# steering_wheel_V3_0.net
KiCad netlist of a schematic drawn in EAGLE
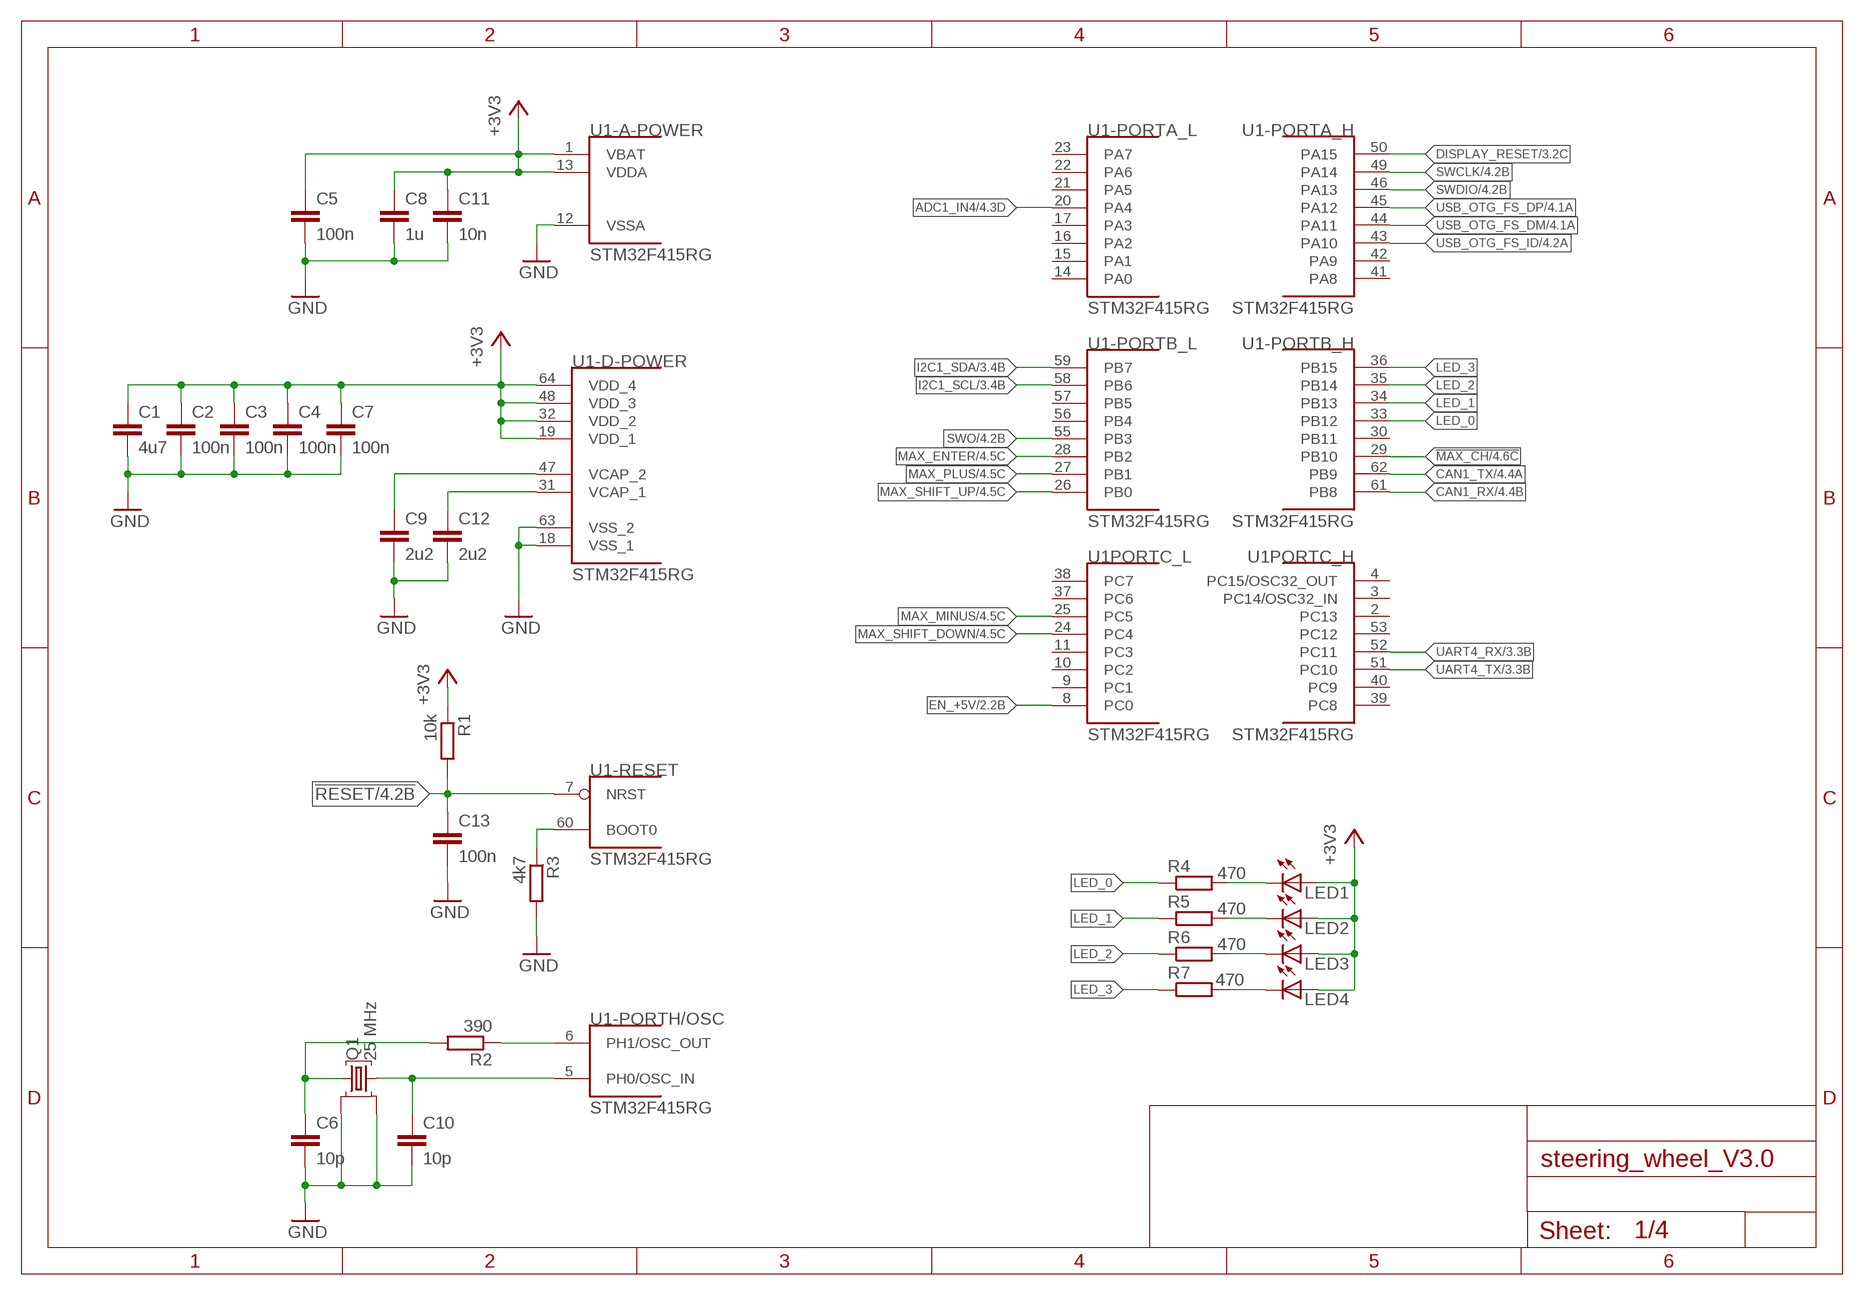
[diagram p0: schematic, sheet 1]
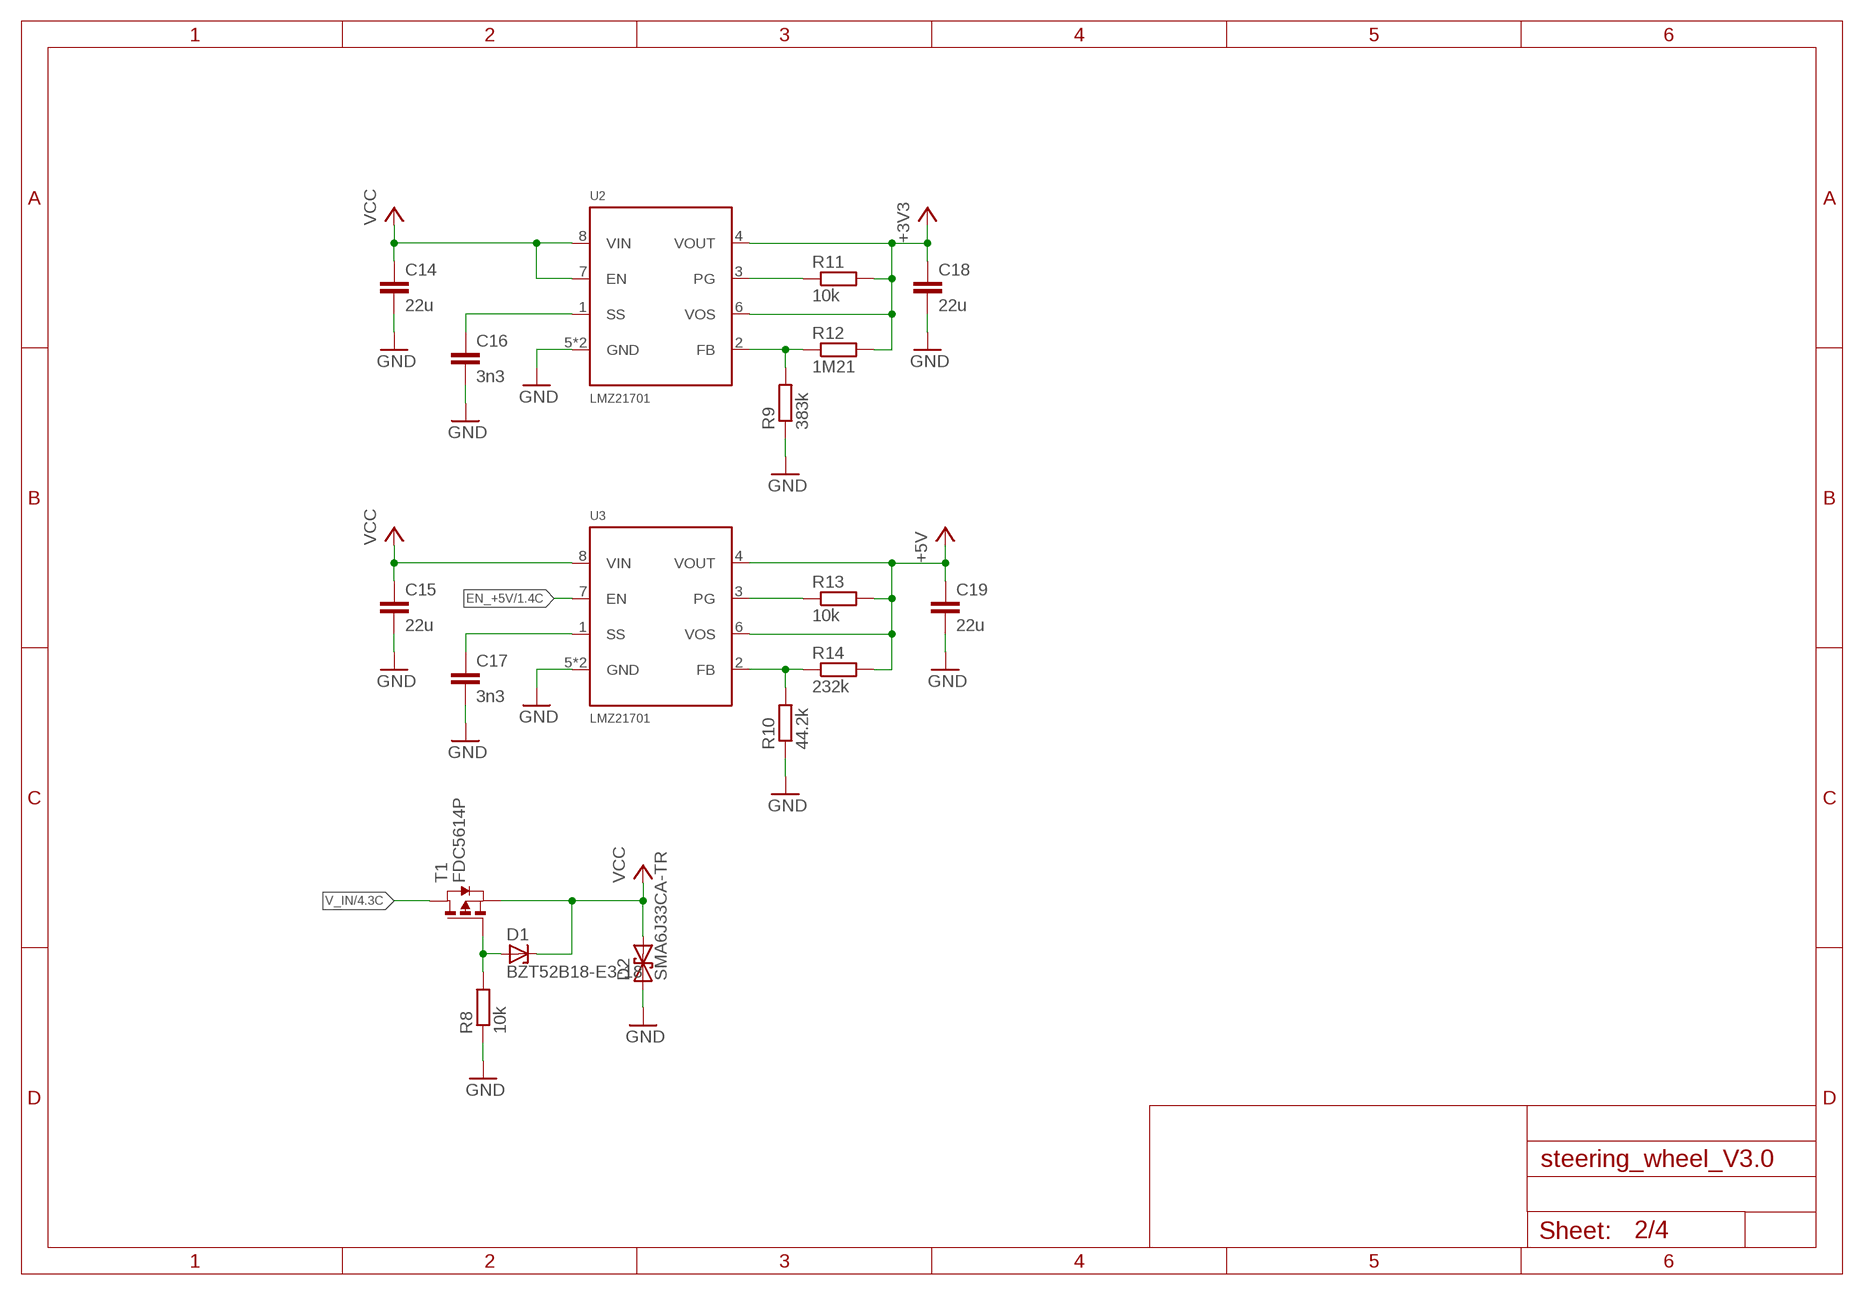
[diagram p1: schematic, sheet 2]
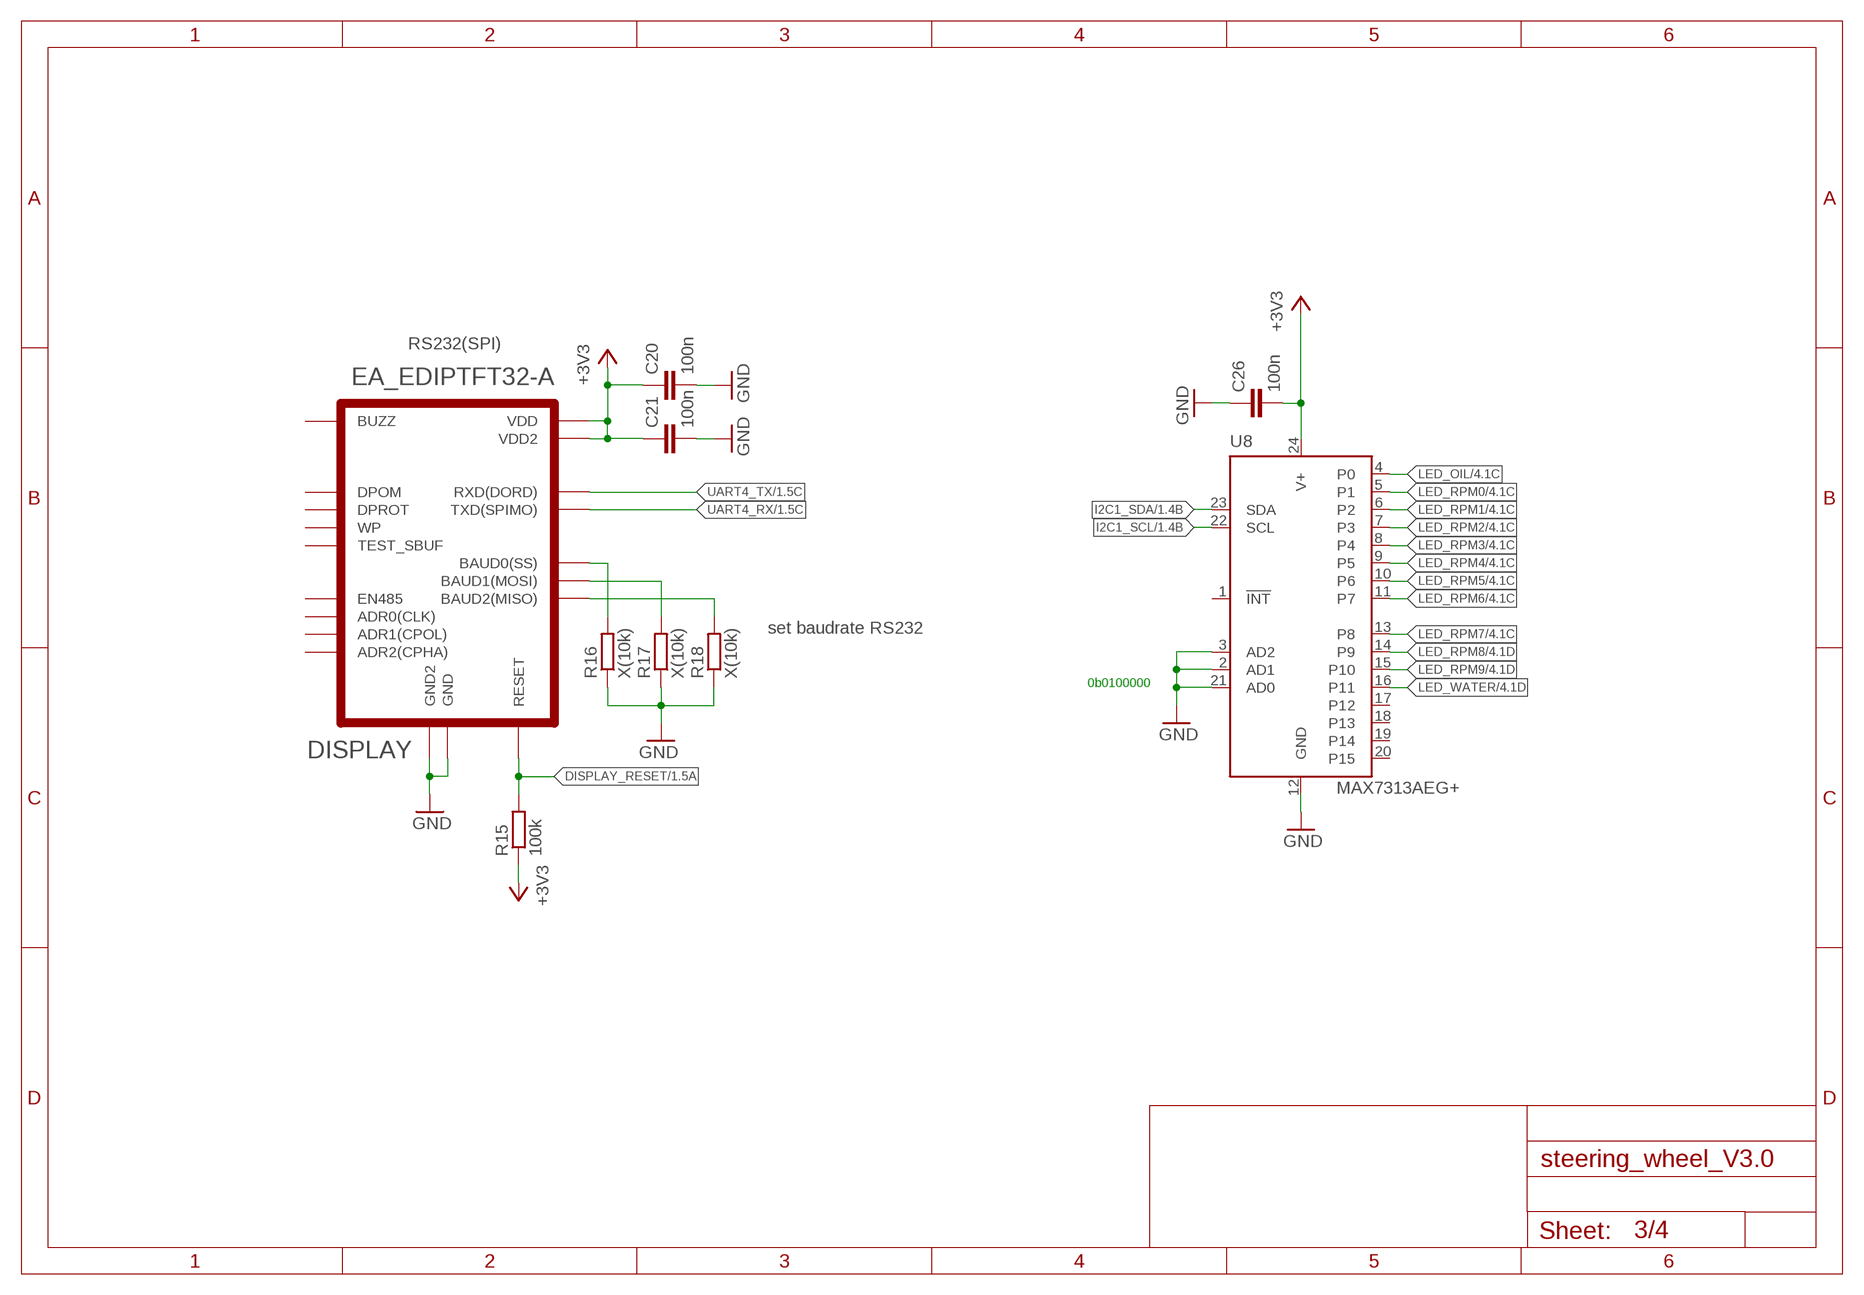
[diagram p2: schematic, sheet 3]
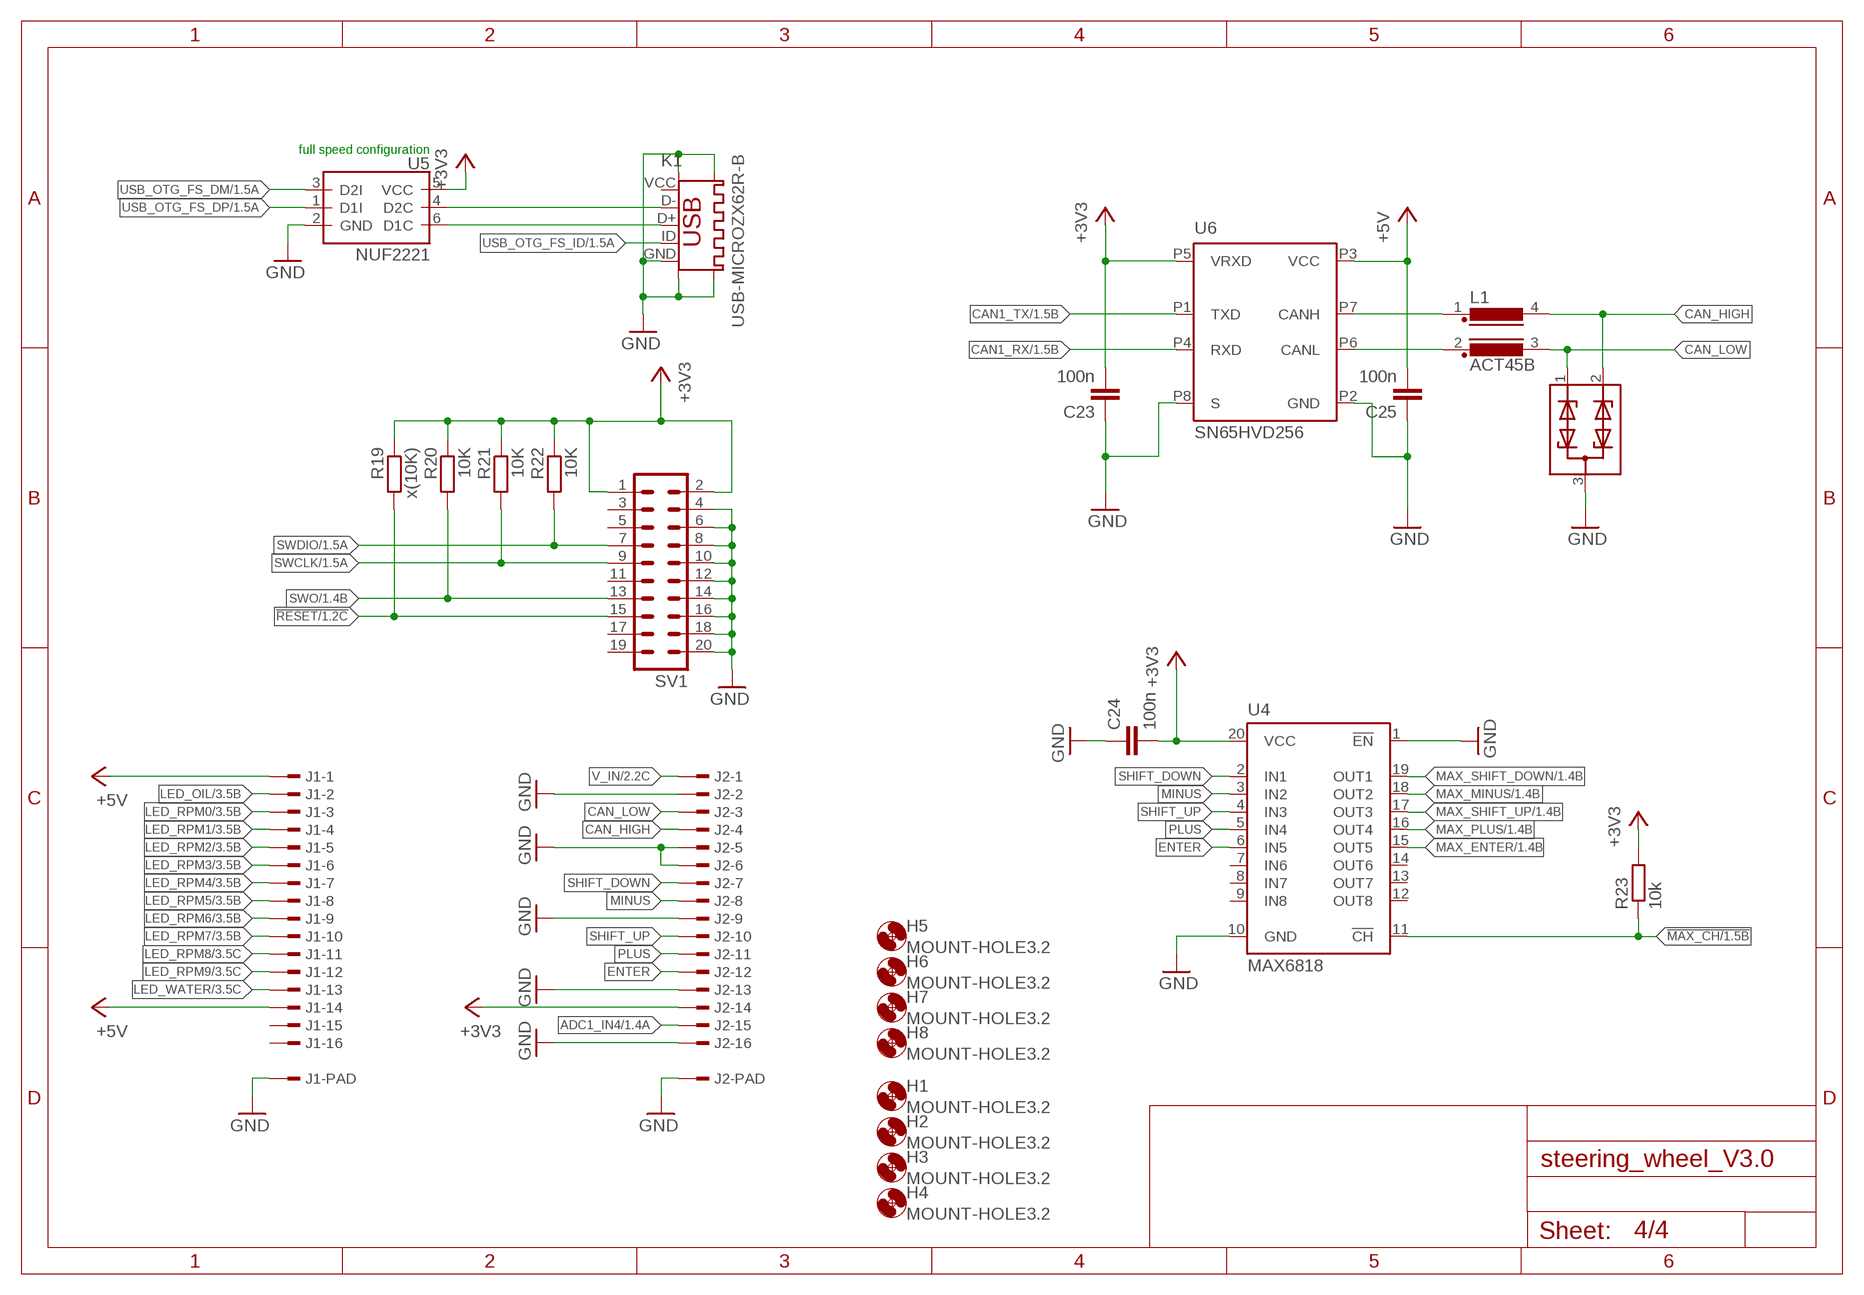
[diagram p3: schematic, sheet 4]

(export (version "E")
  (design (tool "Eeschema 10.0.6"))
  (components
    (comp (ref "C14")
      (value "22u")
      (footprint "eagle-import:C1210")
      (libsource (lib "eagle-import") (part "C-EUC1210"))
    )
    (comp (ref "C15")
      (value "22u")
      (footprint "eagle-import:C1210")
      (libsource (lib "eagle-import") (part "C-EUC1210"))
    )
    (comp (ref "C16")
      (value "3n3")
      (footprint "eagle-import:C0603")
      (libsource (lib "eagle-import") (part "C-EUC0603"))
    )
    (comp (ref "C17")
      (value "3n3")
      (footprint "eagle-import:C0603")
      (libsource (lib "eagle-import") (part "C-EUC0603"))
    )
    (comp (ref "C18")
      (value "22u")
      (footprint "eagle-import:C1210")
      (libsource (lib "eagle-import") (part "C-EUC1210"))
    )
    (comp (ref "C19")
      (value "22u")
      (footprint "eagle-import:C1210")
      (libsource (lib "eagle-import") (part "C-EUC1210"))
    )
    (comp (ref "D1")
      (value "BZT52B18-E3-18")
      (footprint "eagle-import:SOD123F")
      (libsource (lib "eagle-import") (part "ZENER_SOD123"))
    )
    (comp (ref "D2")
      (value "SMA6J33CA-TR")
      (footprint "eagle-import:DO214AC")
      (libsource (lib "eagle-import") (part "SMA6J33CA-TR"))
    )
    (comp (ref "R8")
      (value "10k")
      (footprint "eagle-import:R0603")
      (libsource (lib "eagle-import") (part "R-EU_R0603"))
    )
    (comp (ref "R9")
      (value "383k")
      (footprint "eagle-import:R0603")
      (libsource (lib "eagle-import") (part "R-EU_R0603"))
    )
    (comp (ref "R10")
      (value "44.2k")
      (footprint "eagle-import:R0603")
      (libsource (lib "eagle-import") (part "R-EU_R0603"))
    )
    (comp (ref "R11")
      (value "10k")
      (footprint "eagle-import:R0603")
      (libsource (lib "eagle-import") (part "R-EU_R0603"))
    )
    (comp (ref "R12")
      (value "1M21")
      (footprint "eagle-import:R0603")
      (libsource (lib "eagle-import") (part "R-EU_R0603"))
    )
    (comp (ref "R13")
      (value "10k")
      (footprint "eagle-import:R0603")
      (libsource (lib "eagle-import") (part "R-EU_R0603"))
    )
    (comp (ref "R14")
      (value "232k")
      (footprint "eagle-import:R0603")
      (libsource (lib "eagle-import") (part "R-EU_R0603"))
    )
    (comp (ref "T1")
      (value "FDC5614P")
      (footprint "eagle-import:SSOT6")
      (libsource (lib "eagle-import") (part "FDC5614P"))
    )
    (comp (ref "U2")
      (value "LMZ21701")
      (footprint "eagle-import:SIL0008E")
      (libsource (lib "eagle-import") (part "LMZ21701"))
    )
    (comp (ref "U3")
      (value "LMZ21701")
      (footprint "eagle-import:SIL0008E")
      (libsource (lib "eagle-import") (part "LMZ21701"))
    )
    (comp (ref "C23")
      (value "100n")
      (footprint "eagle-import:C0603")
      (libsource (lib "eagle-import") (part "C-EUC0603"))
    )
    (comp (ref "C24")
      (value "100n")
      (footprint "eagle-import:C0603")
      (libsource (lib "eagle-import") (part "C-EUC0603"))
    )
    (comp (ref "C25")
      (value "100n")
      (footprint "eagle-import:C0603")
      (libsource (lib "eagle-import") (part "C-EUC0603"))
    )
    (comp (ref "D3")
      (value "PESD1CAN-U")
      (footprint "eagle-import:SOT-323")
      (libsource (lib "eagle-import") (part "PESD1CAN-U"))
    )
    (comp (ref "H1")
      (value "MOUNT-HOLE3.2")
      (footprint "eagle-import:3,2")
      (libsource (lib "eagle-import") (part "MOUNT-HOLE3.2"))
    )
    (comp (ref "H2")
      (value "MOUNT-HOLE3.2")
      (footprint "eagle-import:3,2")
      (libsource (lib "eagle-import") (part "MOUNT-HOLE3.2"))
    )
    (comp (ref "H3")
      (value "MOUNT-HOLE3.2")
      (footprint "eagle-import:3,2")
      (libsource (lib "eagle-import") (part "MOUNT-HOLE3.2"))
    )
    (comp (ref "H4")
      (value "MOUNT-HOLE3.2")
      (footprint "eagle-import:3,2")
      (libsource (lib "eagle-import") (part "MOUNT-HOLE3.2"))
    )
    (comp (ref "H5")
      (value "MOUNT-HOLE3.2")
      (footprint "eagle-import:3,2")
      (libsource (lib "eagle-import") (part "MOUNT-HOLE3.2"))
    )
    (comp (ref "H6")
      (value "MOUNT-HOLE3.2")
      (footprint "eagle-import:3,2")
      (libsource (lib "eagle-import") (part "MOUNT-HOLE3.2"))
    )
    (comp (ref "H7")
      (value "MOUNT-HOLE3.2")
      (footprint "eagle-import:3,2")
      (libsource (lib "eagle-import") (part "MOUNT-HOLE3.2"))
    )
    (comp (ref "H8")
      (value "MOUNT-HOLE3.2")
      (footprint "eagle-import:3,2")
      (libsource (lib "eagle-import") (part "MOUNT-HOLE3.2"))
    )
    (comp (ref "J1")
      (value "1-292227-6")
      (footprint "eagle-import:1-292227-6")
      (libsource (lib "eagle-import") (part "1-292227-6"))
    )
    (comp (ref "J2")
      (value "1-292227-6")
      (footprint "eagle-import:1-292227-6")
      (libsource (lib "eagle-import") (part "1-292227-6"))
    )
    (comp (ref "K1")
      (value "USB-MICROZX62R-B")
      (footprint "eagle-import:ZX62R-B")
      (libsource (lib "eagle-import") (part "USB-MICROZX62R-B"))
    )
    (comp (ref "L1")
      (value "ACT45B")
      (footprint "eagle-import:ACT45B")
      (libsource (lib "eagle-import") (part "ACT45B"))
    )
    (comp (ref "R19")
      (value "x(10K)")
      (footprint "eagle-import:R0603")
      (libsource (lib "eagle-import") (part "R-EU_R0603"))
    )
    (comp (ref "R20")
      (value "10K")
      (footprint "eagle-import:R0603")
      (libsource (lib "eagle-import") (part "R-EU_R0603"))
    )
    (comp (ref "R21")
      (value "10K")
      (footprint "eagle-import:R0603")
      (libsource (lib "eagle-import") (part "R-EU_R0603"))
    )
    (comp (ref "R22")
      (value "10K")
      (footprint "eagle-import:R0603")
      (libsource (lib "eagle-import") (part "R-EU_R0603"))
    )
    (comp (ref "R23")
      (value "10k")
      (footprint "eagle-import:R0603")
      (libsource (lib "eagle-import") (part "R-EU_R0603"))
    )
    (comp (ref "SV1")
      (value "ML20")
      (footprint "eagle-import:ML20")
      (libsource (lib "eagle-import") (part "ML20"))
    )
    (comp (ref "U4")
      (value "MAX6818")
      (footprint "eagle-import:SSOP-20")
      (libsource (lib "eagle-import") (part "MAX6818"))
    )
    (comp (ref "U5")
      (value "NUF2221")
      (footprint "eagle-import:SOT363")
      (fields
        (field (name "OC_DIGIKEY") "NUF2221W1T2GOSCT-ND")
        (field (name "ORDER_CODE") "NUF2221W1T2GOSCT-ND")
      )
      (libsource (lib "eagle-import") (part "NUF2221"))
    )
    (comp (ref "U6")
      (value "SN65HVD256")
      (footprint "eagle-import:SOIC8")
      (libsource (lib "eagle-import") (part "SN65HVD256"))
    )
    (comp (ref "C1")
      (value "4u7")
      (footprint "eagle-import:C0603")
      (libsource (lib "eagle-import") (part "C-EUC0603"))
    )
    (comp (ref "C2")
      (value "100n")
      (footprint "eagle-import:C0603")
      (libsource (lib "eagle-import") (part "C-EUC0603"))
    )
    (comp (ref "C3")
      (value "100n")
      (footprint "eagle-import:C0603")
      (libsource (lib "eagle-import") (part "C-EUC0603"))
    )
    (comp (ref "C4")
      (value "100n")
      (footprint "eagle-import:C0603")
      (libsource (lib "eagle-import") (part "C-EUC0603"))
    )
    (comp (ref "C5")
      (value "100n")
      (footprint "eagle-import:C0603")
      (libsource (lib "eagle-import") (part "C-EUC0603"))
    )
    (comp (ref "C6")
      (value "10p")
      (footprint "eagle-import:C0603")
      (libsource (lib "eagle-import") (part "C-EUC0603"))
    )
    (comp (ref "C7")
      (value "100n")
      (footprint "eagle-import:C0603")
      (libsource (lib "eagle-import") (part "C-EUC0603"))
    )
    (comp (ref "C8")
      (value "1u")
      (footprint "eagle-import:C0603")
      (libsource (lib "eagle-import") (part "C-EUC0603"))
    )
    (comp (ref "C9")
      (value "2u2")
      (footprint "eagle-import:C0603")
      (libsource (lib "eagle-import") (part "C-EUC0603"))
    )
    (comp (ref "C10")
      (value "10p")
      (footprint "eagle-import:C0603")
      (libsource (lib "eagle-import") (part "C-EUC0603"))
    )
    (comp (ref "C11")
      (value "10n")
      (footprint "eagle-import:C0603")
      (libsource (lib "eagle-import") (part "C-EUC0603"))
    )
    (comp (ref "C12")
      (value "2u2")
      (footprint "eagle-import:C0603")
      (libsource (lib "eagle-import") (part "C-EUC0603"))
    )
    (comp (ref "C13")
      (value "100n")
      (footprint "eagle-import:C0603")
      (libsource (lib "eagle-import") (part "C-EUC0603"))
    )
    (comp (ref "LED1")
      (value "LEDCHIPLED_0603")
      (footprint "eagle-import:CHIPLED_0603")
      (libsource (lib "eagle-import") (part "LEDCHIPLED_0603"))
    )
    (comp (ref "LED2")
      (value "LEDCHIPLED_0603")
      (footprint "eagle-import:CHIPLED_0603")
      (libsource (lib "eagle-import") (part "LEDCHIPLED_0603"))
    )
    (comp (ref "LED3")
      (value "LEDCHIPLED_0603")
      (footprint "eagle-import:CHIPLED_0603")
      (libsource (lib "eagle-import") (part "LEDCHIPLED_0603"))
    )
    (comp (ref "LED4")
      (value "LEDCHIPLED_0603")
      (footprint "eagle-import:CHIPLED_0603")
      (libsource (lib "eagle-import") (part "LEDCHIPLED_0603"))
    )
    (comp (ref "Q1")
      (value "25 MHz")
      (footprint "eagle-import:3.2X2.5MM-SMD")
      (libsource (lib "eagle-import") (part "CRYSTAL2M_CX32"))
    )
    (comp (ref "R1")
      (value "10k")
      (footprint "eagle-import:R0603")
      (libsource (lib "eagle-import") (part "R-EU_R0603"))
    )
    (comp (ref "R2")
      (value "390")
      (footprint "eagle-import:R0603")
      (libsource (lib "eagle-import") (part "R-EU_R0603"))
    )
    (comp (ref "R3")
      (value "4k7")
      (footprint "eagle-import:R0603")
      (libsource (lib "eagle-import") (part "R-EU_R0603"))
    )
    (comp (ref "R4")
      (value "470")
      (footprint "eagle-import:R0603")
      (libsource (lib "eagle-import") (part "R-EU_R0603"))
    )
    (comp (ref "R5")
      (value "470")
      (footprint "eagle-import:R0603")
      (libsource (lib "eagle-import") (part "R-EU_R0603"))
    )
    (comp (ref "R6")
      (value "470")
      (footprint "eagle-import:R0603")
      (libsource (lib "eagle-import") (part "R-EU_R0603"))
    )
    (comp (ref "R7")
      (value "470")
      (footprint "eagle-import:R0603")
      (libsource (lib "eagle-import") (part "R-EU_R0603"))
    )
    (comp (ref "U1")
      (value "STM32F415RG")
      (footprint "eagle-import:LQFP64")
      (libsource (lib "eagle-import") (part "STM32F415RG"))
    )
    (comp (ref "C20")
      (value "100n")
      (footprint "eagle-import:C0603")
      (libsource (lib "eagle-import") (part "C-EUC0603"))
    )
    (comp (ref "C21")
      (value "100n")
      (footprint "eagle-import:C0603")
      (libsource (lib "eagle-import") (part "C-EUC0603"))
    )
    (comp (ref "C26")
      (value "100n")
      (footprint "eagle-import:C0603")
      (libsource (lib "eagle-import") (part "C-EUC0603"))
    )
    (comp (ref "DISPLAY")
      (value "EA_EDIPTFT32-A")
      (footprint "eagle-import:EDIPTFT32-A")
      (libsource (lib "eagle-import") (part "EA_EDIPTFT32-A-SR232"))
    )
    (comp (ref "R15")
      (value "100k")
      (footprint "eagle-import:R0603")
      (libsource (lib "eagle-import") (part "R-EU_R0603"))
    )
    (comp (ref "R16")
      (value "X(10k)")
      (footprint "eagle-import:R0603")
      (libsource (lib "eagle-import") (part "R-EU_R0603"))
    )
    (comp (ref "R17")
      (value "X(10k)")
      (footprint "eagle-import:R0603")
      (libsource (lib "eagle-import") (part "R-EU_R0603"))
    )
    (comp (ref "R18")
      (value "X(10k)")
      (footprint "eagle-import:R0603")
      (libsource (lib "eagle-import") (part "R-EU_R0603"))
    )
    (comp (ref "U8")
      (value "MAX7313AEG+")
      (footprint "eagle-import:QSOP-24")
      (libsource (lib "eagle-import") (part "MAX7313AEG+"))
    )
  )
  (nets
    (net (code "1") (name "+3V3") (class "Default")
      (node (ref "C1") (pin "1") (pinfunction "1_1") (pintype "passive"))
      (node (ref "C11") (pin "1") (pinfunction "1_1") (pintype "passive"))
      (node (ref "C18") (pin "1") (pinfunction "1_1") (pintype "passive"))
      (node (ref "C2") (pin "1") (pinfunction "1_1") (pintype "passive"))
      (node (ref "C20") (pin "1") (pinfunction "1_1") (pintype "passive"))
      (node (ref "C21") (pin "1") (pinfunction "1_1") (pintype "passive"))
      (node (ref "C23") (pin "2") (pinfunction "2_2") (pintype "passive"))
      (node (ref "C24") (pin "2") (pinfunction "2_2") (pintype "passive"))
      (node (ref "C26") (pin "2") (pinfunction "2_2") (pintype "passive"))
      (node (ref "C3") (pin "1") (pinfunction "1_1") (pintype "passive"))
      (node (ref "C4") (pin "1") (pinfunction "1_1") (pintype "passive"))
      (node (ref "C5") (pin "1") (pinfunction "1_1") (pintype "passive"))
      (node (ref "C7") (pin "1") (pinfunction "1_1") (pintype "passive"))
      (node (ref "C8") (pin "1") (pinfunction "1_1") (pintype "passive"))
      (node (ref "DISPLAY") (pin "P$2") (pinfunction "VDD_P$2") (pintype "bidirectional"))
      (node (ref "DISPLAY") (pin "P$22") (pinfunction "VDD2_P$22") (pintype "bidirectional"))
      (node (ref "J2") (pin "14") (pinfunction "1_14") (pintype "passive"))
      (node (ref "LED1") (pin "A") (pinfunction "A_A") (pintype "passive"))
      (node (ref "LED2") (pin "A") (pinfunction "A_A") (pintype "passive"))
      (node (ref "LED3") (pin "A") (pinfunction "A_A") (pintype "passive"))
      (node (ref "LED4") (pin "A") (pinfunction "A_A") (pintype "passive"))
      (node (ref "R1") (pin "1") (pinfunction "1_1") (pintype "passive"))
      (node (ref "R11") (pin "2") (pinfunction "2_2") (pintype "passive"))
      (node (ref "R12") (pin "2") (pinfunction "2_2") (pintype "passive"))
      (node (ref "R15") (pin "1") (pinfunction "1_1") (pintype "passive"))
      (node (ref "R19") (pin "1") (pinfunction "1_1") (pintype "passive"))
      (node (ref "R20") (pin "1") (pinfunction "1_1") (pintype "passive"))
      (node (ref "R21") (pin "1") (pinfunction "1_1") (pintype "passive"))
      (node (ref "R22") (pin "1") (pinfunction "1_1") (pintype "passive"))
      (node (ref "R23") (pin "2") (pinfunction "2_2") (pintype "passive"))
      (node (ref "SV1") (pin "1") (pinfunction "1_1") (pintype "passive"))
      (node (ref "SV1") (pin "2") (pinfunction "2_2") (pintype "passive"))
      (node (ref "U1") (pin "1") (pinfunction "VBAT_1") (pintype "power_in"))
      (node (ref "U1") (pin "13") (pinfunction "VDDA_13") (pintype "power_in"))
      (node (ref "U1") (pin "19") (pinfunction "VDD_1_19") (pintype "power_in"))
      (node (ref "U1") (pin "32") (pinfunction "VDD_2_32") (pintype "power_in"))
      (node (ref "U1") (pin "48") (pinfunction "VDD_3_48") (pintype "power_in"))
      (node (ref "U1") (pin "64") (pinfunction "VDD_4_64") (pintype "power_in"))
      (node (ref "U2") (pin "4") (pinfunction "VOUT_4") (pintype "passive"))
      (node (ref "U2") (pin "6") (pinfunction "VOS_6") (pintype "input"))
      (node (ref "U4") (pin "20") (pinfunction "VCC_20") (pintype "bidirectional"))
      (node (ref "U5") (pin "5") (pinfunction "VCC_5") (pintype "power_in"))
      (node (ref "U6") (pin "P5") (pinfunction "VRXD_P5") (pintype "power_in"))
      (node (ref "U8") (pin "24") (pinfunction "V+_24") (pintype "power_in"))
    )
    (net (code "2") (name "+5V") (class "Default")
      (node (ref "C19") (pin "1") (pinfunction "1_1") (pintype "passive"))
      (node (ref "C25") (pin "2") (pinfunction "2_2") (pintype "passive"))
      (node (ref "J1") (pin "1") (pinfunction "1_1") (pintype "passive"))
      (node (ref "J1") (pin "14") (pinfunction "1_14") (pintype "passive"))
      (node (ref "R13") (pin "2") (pinfunction "2_2") (pintype "passive"))
      (node (ref "R14") (pin "2") (pinfunction "2_2") (pintype "passive"))
      (node (ref "U3") (pin "4") (pinfunction "VOUT_4") (pintype "passive"))
      (node (ref "U3") (pin "6") (pinfunction "VOS_6") (pintype "input"))
      (node (ref "U6") (pin "P3") (pinfunction "VCC_P3") (pintype "power_in"))
    )
    (net (code "3") (name "ADC1_IN4") (class "Default")
      (node (ref "J2") (pin "15") (pinfunction "1_15") (pintype "passive"))
      (node (ref "U1") (pin "20") (pinfunction "PA4_20") (pintype "bidirectional"))
    )
    (net (code "4") (name "CAN1_RX") (class "Default")
      (node (ref "U1") (pin "61") (pinfunction "PB8_61") (pintype "bidirectional"))
      (node (ref "U6") (pin "P4") (pinfunction "RXD_P4") (pintype "output"))
    )
    (net (code "5") (name "CAN1_TX") (class "Default")
      (node (ref "U1") (pin "62") (pinfunction "PB9_62") (pintype "bidirectional"))
      (node (ref "U6") (pin "P1") (pinfunction "TXD_P1") (pintype "input"))
    )
    (net (code "6") (name "CAN_HIGH") (class "Default")
      (node (ref "D3") (pin "2") (pinfunction "2_2") (pintype "passive"))
      (node (ref "J2") (pin "4") (pinfunction "1_4") (pintype "passive"))
      (node (ref "L1") (pin "4") (pinfunction "4_4") (pintype "passive"))
    )
    (net (code "7") (name "CAN_LOW") (class "Default")
      (node (ref "D3") (pin "1") (pinfunction "1_1") (pintype "passive"))
      (node (ref "J2") (pin "3") (pinfunction "1_3") (pintype "passive"))
      (node (ref "L1") (pin "3") (pinfunction "3_3") (pintype "passive"))
    )
    (net (code "8") (name "DISPLAY_RESET") (class "Default")
      (node (ref "DISPLAY") (pin "P$5") (pinfunction "RESET_P$5") (pintype "bidirectional"))
      (node (ref "R15") (pin "2") (pinfunction "2_2") (pintype "passive"))
      (node (ref "U1") (pin "50") (pinfunction "PA15_50") (pintype "bidirectional"))
    )
    (net (code "9") (name "ENTER") (class "Default")
      (node (ref "J2") (pin "12") (pinfunction "1_12") (pintype "passive"))
      (node (ref "U4") (pin "6") (pinfunction "IN5_6") (pintype "bidirectional"))
    )
    (net (code "10") (name "EN_+5V") (class "Default")
      (node (ref "U1") (pin "8") (pinfunction "PC0_8") (pintype "bidirectional"))
      (node (ref "U3") (pin "7") (pinfunction "EN_7") (pintype "input"))
    )
    (net (code "11") (name "GND") (class "Default")
      (node (ref "C1") (pin "2") (pinfunction "2_2") (pintype "passive"))
      (node (ref "C10") (pin "2") (pinfunction "2_2") (pintype "passive"))
      (node (ref "C11") (pin "2") (pinfunction "2_2") (pintype "passive"))
      (node (ref "C12") (pin "2") (pinfunction "2_2") (pintype "passive"))
      (node (ref "C13") (pin "2") (pinfunction "2_2") (pintype "passive"))
      (node (ref "C14") (pin "2") (pinfunction "2_2") (pintype "passive"))
      (node (ref "C15") (pin "2") (pinfunction "2_2") (pintype "passive"))
      (node (ref "C16") (pin "2") (pinfunction "2_2") (pintype "passive"))
      (node (ref "C17") (pin "2") (pinfunction "2_2") (pintype "passive"))
      (node (ref "C18") (pin "2") (pinfunction "2_2") (pintype "passive"))
      (node (ref "C19") (pin "2") (pinfunction "2_2") (pintype "passive"))
      (node (ref "C2") (pin "2") (pinfunction "2_2") (pintype "passive"))
      (node (ref "C20") (pin "2") (pinfunction "2_2") (pintype "passive"))
      (node (ref "C21") (pin "2") (pinfunction "2_2") (pintype "passive"))
      (node (ref "C23") (pin "1") (pinfunction "1_1") (pintype "passive"))
      (node (ref "C24") (pin "1") (pinfunction "1_1") (pintype "passive"))
      (node (ref "C25") (pin "1") (pinfunction "1_1") (pintype "passive"))
      (node (ref "C26") (pin "1") (pinfunction "1_1") (pintype "passive"))
      (node (ref "C3") (pin "2") (pinfunction "2_2") (pintype "passive"))
      (node (ref "C4") (pin "2") (pinfunction "2_2") (pintype "passive"))
      (node (ref "C5") (pin "2") (pinfunction "2_2") (pintype "passive"))
      (node (ref "C6") (pin "2") (pinfunction "2_2") (pintype "passive"))
      (node (ref "C7") (pin "2") (pinfunction "2_2") (pintype "passive"))
      (node (ref "C8") (pin "2") (pinfunction "2_2") (pintype "passive"))
      (node (ref "C9") (pin "2") (pinfunction "2_2") (pintype "passive"))
      (node (ref "D2") (pin "A") (pinfunction "1_A") (pintype "passive"))
      (node (ref "D3") (pin "3") (pinfunction "3_3") (pintype "passive"))
      (node (ref "DISPLAY") (pin "P$1") (pinfunction "GND_P$1") (pintype "bidirectional"))
      (node (ref "DISPLAY") (pin "P$21") (pinfunction "GND2_P$21") (pintype "bidirectional"))
      (node (ref "J1") (pin "PAD1") (pinfunction "1_PAD1") (pintype "passive"))
      (node (ref "J1") (pin "PAD2") (pinfunction "1_PAD2") (pintype "passive"))
      (node (ref "J2") (pin "13") (pinfunction "1_13") (pintype "passive"))
      (node (ref "J2") (pin "16") (pinfunction "1_16") (pintype "passive"))
      (node (ref "J2") (pin "2") (pinfunction "1_2") (pintype "passive"))
      (node (ref "J2") (pin "5") (pinfunction "1_5") (pintype "passive"))
      (node (ref "J2") (pin "6") (pinfunction "1_6") (pintype "passive"))
      (node (ref "J2") (pin "9") (pinfunction "1_9") (pintype "passive"))
      (node (ref "J2") (pin "PAD1") (pinfunction "1_PAD1") (pintype "passive"))
      (node (ref "J2") (pin "PAD2") (pinfunction "1_PAD2") (pintype "passive"))
      (node (ref "K1") (pin "GND") (pinfunction "GND_GND") (pintype "passive"))
      (node (ref "K1") (pin "P$6") (pinfunction "GND3_P$6") (pintype "bidirectional"))
      (node (ref "K1") (pin "P$7") (pinfunction "GND4_P$7") (pintype "bidirectional"))
      (node (ref "K1") (pin "P$8") (pinfunction "GND1_P$8") (pintype "bidirectional"))
      (node (ref "K1") (pin "P$9") (pinfunction "GND2_P$9") (pintype "bidirectional"))
      (node (ref "Q1") (pin "2") (pinfunction "GND1_2") (pintype "power_in"))
      (node (ref "Q1") (pin "4") (pinfunction "GND2_4") (pintype "power_in"))
      (node (ref "R10") (pin "1") (pinfunction "1_1") (pintype "passive"))
      (node (ref "R16") (pin "1") (pinfunction "1_1") (pintype "passive"))
      (node (ref "R17") (pin "1") (pinfunction "1_1") (pintype "passive"))
      (node (ref "R18") (pin "1") (pinfunction "1_1") (pintype "passive"))
      (node (ref "R3") (pin "2") (pinfunction "2_2") (pintype "passive"))
      (node (ref "R8") (pin "1") (pinfunction "1_1") (pintype "passive"))
      (node (ref "R9") (pin "1") (pinfunction "1_1") (pintype "passive"))
      (node (ref "SV1") (pin "10") (pinfunction "10_10") (pintype "passive"))
      (node (ref "SV1") (pin "12") (pinfunction "12_12") (pintype "passive"))
      (node (ref "SV1") (pin "14") (pinfunction "14_14") (pintype "passive"))
      (node (ref "SV1") (pin "16") (pinfunction "16_16") (pintype "passive"))
      (node (ref "SV1") (pin "18") (pinfunction "18_18") (pintype "passive"))
      (node (ref "SV1") (pin "20") (pinfunction "20_20") (pintype "passive"))
      (node (ref "SV1") (pin "4") (pinfunction "4_4") (pintype "passive"))
      (node (ref "SV1") (pin "6") (pinfunction "6_6") (pintype "passive"))
      (node (ref "SV1") (pin "8") (pinfunction "8_8") (pintype "passive"))
      (node (ref "U1") (pin "12") (pinfunction "VSSA_12") (pintype "power_in"))
      (node (ref "U1") (pin "18") (pinfunction "VSS_1_18") (pintype "power_in"))
      (node (ref "U1") (pin "63") (pinfunction "VSS_2_63") (pintype "power_in"))
      (node (ref "U2") (pin "5") (pinfunction "GND_5") (pintype "power_in"))
      (node (ref "U2") (pin "PAD") (pinfunction "GND_PAD") (pintype "power_in"))
      (node (ref "U3") (pin "5") (pinfunction "GND_5") (pintype "power_in"))
      (node (ref "U3") (pin "PAD") (pinfunction "GND_PAD") (pintype "power_in"))
      (node (ref "U4") (pin "1") (pinfunction "~{EN}_1") (pintype "bidirectional"))
      (node (ref "U4") (pin "10") (pinfunction "GND_10") (pintype "bidirectional"))
      (node (ref "U5") (pin "2") (pinfunction "GND_2") (pintype "power_in"))
      (node (ref "U6") (pin "P2") (pinfunction "GND_P2") (pintype "power_in"))
      (node (ref "U6") (pin "P8") (pinfunction "S_P8") (pintype "input"))
      (node (ref "U8") (pin "12") (pinfunction "GND_12") (pintype "power_in"))
      (node (ref "U8") (pin "2") (pinfunction "AD1_2") (pintype "bidirectional"))
      (node (ref "U8") (pin "21") (pinfunction "AD0_21") (pintype "bidirectional"))
      (node (ref "U8") (pin "3") (pinfunction "AD2_3") (pintype "bidirectional"))
    )
    (net (code "12") (name "I2C1_SCL") (class "Default")
      (node (ref "U1") (pin "58") (pinfunction "PB6_58") (pintype "bidirectional"))
      (node (ref "U8") (pin "22") (pinfunction "SCL_22") (pintype "bidirectional"))
    )
    (net (code "13") (name "I2C1_SDA") (class "Default")
      (node (ref "U1") (pin "59") (pinfunction "PB7_59") (pintype "bidirectional"))
      (node (ref "U8") (pin "23") (pinfunction "SDA_23") (pintype "bidirectional"))
    )
    (net (code "14") (name "LED_0") (class "Default")
      (node (ref "R4") (pin "1") (pinfunction "1_1") (pintype "passive"))
      (node (ref "U1") (pin "33") (pinfunction "PB12_33") (pintype "bidirectional"))
    )
    (net (code "15") (name "LED_1") (class "Default")
      (node (ref "R5") (pin "1") (pinfunction "1_1") (pintype "passive"))
      (node (ref "U1") (pin "34") (pinfunction "PB13_34") (pintype "bidirectional"))
    )
    (net (code "16") (name "LED_2") (class "Default")
      (node (ref "R6") (pin "1") (pinfunction "1_1") (pintype "passive"))
      (node (ref "U1") (pin "35") (pinfunction "PB14_35") (pintype "bidirectional"))
    )
    (net (code "17") (name "LED_3") (class "Default")
      (node (ref "R7") (pin "1") (pinfunction "1_1") (pintype "passive"))
      (node (ref "U1") (pin "36") (pinfunction "PB15_36") (pintype "bidirectional"))
    )
    (net (code "18") (name "LED_OIL") (class "Default")
      (node (ref "J1") (pin "2") (pinfunction "1_2") (pintype "passive"))
      (node (ref "U8") (pin "4") (pinfunction "P0_4") (pintype "passive"))
    )
    (net (code "19") (name "LED_RPM0") (class "Default")
      (node (ref "J1") (pin "3") (pinfunction "1_3") (pintype "passive"))
      (node (ref "U8") (pin "5") (pinfunction "P1_5") (pintype "passive"))
    )
    (net (code "20") (name "LED_RPM1") (class "Default")
      (node (ref "J1") (pin "4") (pinfunction "1_4") (pintype "passive"))
      (node (ref "U8") (pin "6") (pinfunction "P2_6") (pintype "passive"))
    )
    (net (code "21") (name "LED_RPM2") (class "Default")
      (node (ref "J1") (pin "5") (pinfunction "1_5") (pintype "passive"))
      (node (ref "U8") (pin "7") (pinfunction "P3_7") (pintype "passive"))
    )
    (net (code "22") (name "LED_RPM3") (class "Default")
      (node (ref "J1") (pin "6") (pinfunction "1_6") (pintype "passive"))
      (node (ref "U8") (pin "8") (pinfunction "P4_8") (pintype "passive"))
    )
    (net (code "23") (name "LED_RPM4") (class "Default")
      (node (ref "J1") (pin "7") (pinfunction "1_7") (pintype "passive"))
      (node (ref "U8") (pin "9") (pinfunction "P5_9") (pintype "passive"))
    )
    (net (code "24") (name "LED_RPM5") (class "Default")
      (node (ref "J1") (pin "8") (pinfunction "1_8") (pintype "passive"))
      (node (ref "U8") (pin "10") (pinfunction "P6_10") (pintype "passive"))
    )
    (net (code "25") (name "LED_RPM6") (class "Default")
      (node (ref "J1") (pin "9") (pinfunction "1_9") (pintype "passive"))
      (node (ref "U8") (pin "11") (pinfunction "P7_11") (pintype "passive"))
    )
    (net (code "26") (name "LED_RPM7") (class "Default")
      (node (ref "J1") (pin "10") (pinfunction "1_10") (pintype "passive"))
      (node (ref "U8") (pin "13") (pinfunction "P8_13") (pintype "passive"))
    )
    (net (code "27") (name "LED_RPM8") (class "Default")
      (node (ref "J1") (pin "11") (pinfunction "1_11") (pintype "passive"))
      (node (ref "U8") (pin "14") (pinfunction "P9_14") (pintype "passive"))
    )
    (net (code "28") (name "LED_RPM9") (class "Default")
      (node (ref "J1") (pin "12") (pinfunction "1_12") (pintype "passive"))
      (node (ref "U8") (pin "15") (pinfunction "P10_15") (pintype "passive"))
    )
    (net (code "29") (name "LED_WATER") (class "Default")
      (node (ref "J1") (pin "13") (pinfunction "1_13") (pintype "passive"))
      (node (ref "U8") (pin "16") (pinfunction "P11_16") (pintype "passive"))
    )
    (net (code "30") (name "MAX_ENTER") (class "Default")
      (node (ref "U1") (pin "28") (pinfunction "PB2_28") (pintype "bidirectional"))
      (node (ref "U4") (pin "15") (pinfunction "OUT5_15") (pintype "bidirectional"))
    )
    (net (code "31") (name "MAX_MINUS") (class "Default")
      (node (ref "U1") (pin "25") (pinfunction "PC5_25") (pintype "bidirectional"))
      (node (ref "U4") (pin "18") (pinfunction "OUT2_18") (pintype "bidirectional"))
    )
    (net (code "32") (name "MAX_PLUS") (class "Default")
      (node (ref "U1") (pin "27") (pinfunction "PB1_27") (pintype "bidirectional"))
      (node (ref "U4") (pin "16") (pinfunction "OUT4_16") (pintype "bidirectional"))
    )
    (net (code "33") (name "MAX_SHIFT_DOWN") (class "Default")
      (node (ref "U1") (pin "24") (pinfunction "PC4_24") (pintype "bidirectional"))
      (node (ref "U4") (pin "19") (pinfunction "OUT1_19") (pintype "bidirectional"))
    )
    (net (code "34") (name "MAX_SHIFT_UP") (class "Default")
      (node (ref "U1") (pin "26") (pinfunction "PB0_26") (pintype "bidirectional"))
      (node (ref "U4") (pin "17") (pinfunction "OUT3_17") (pintype "bidirectional"))
    )
    (net (code "35") (name "MINUS") (class "Default")
      (node (ref "J2") (pin "8") (pinfunction "1_8") (pintype "passive"))
      (node (ref "U4") (pin "3") (pinfunction "IN2_3") (pintype "bidirectional"))
    )
    (net (code "36") (name "Net-(DISPLAY-BAUD0(SS))") (class "Default")
      (node (ref "DISPLAY") (pin "P$6") (pinfunction "BAUD0(SS)_P$6") (pintype "bidirectional"))
      (node (ref "R16") (pin "2") (pinfunction "2_2") (pintype "passive"))
    )
    (net (code "37") (name "Net-(DISPLAY-BAUD1(MOSI))") (class "Default")
      (node (ref "DISPLAY") (pin "P$7") (pinfunction "BAUD1(MOSI)_P$7") (pintype "bidirectional"))
      (node (ref "R17") (pin "2") (pinfunction "2_2") (pintype "passive"))
    )
    (net (code "38") (name "Net-(DISPLAY-BAUD2(MISO))") (class "Default")
      (node (ref "DISPLAY") (pin "P$8") (pinfunction "BAUD2(MISO)_P$8") (pintype "bidirectional"))
      (node (ref "R18") (pin "2") (pinfunction "2_2") (pintype "passive"))
    )
    (net (code "39") (name "Net-(LED1-PadC)") (class "Default")
      (node (ref "LED1") (pin "C") (pinfunction "C_C") (pintype "passive"))
      (node (ref "R4") (pin "2") (pinfunction "2_2") (pintype "passive"))
    )
    (net (code "40") (name "Net-(LED2-PadC)") (class "Default")
      (node (ref "LED2") (pin "C") (pinfunction "C_C") (pintype "passive"))
      (node (ref "R5") (pin "2") (pinfunction "2_2") (pintype "passive"))
    )
    (net (code "41") (name "Net-(LED3-PadC)") (class "Default")
      (node (ref "LED3") (pin "C") (pinfunction "C_C") (pintype "passive"))
      (node (ref "R6") (pin "2") (pinfunction "2_2") (pintype "passive"))
    )
    (net (code "42") (name "Net-(LED4-PadC)") (class "Default")
      (node (ref "LED4") (pin "C") (pinfunction "C_C") (pintype "passive"))
      (node (ref "R7") (pin "2") (pinfunction "2_2") (pintype "passive"))
    )
    (net (code "43") (name "Net-(Q1-Q1)") (class "Default")
      (node (ref "C6") (pin "1") (pinfunction "1_1") (pintype "passive"))
      (node (ref "Q1") (pin "1") (pinfunction "Q1_1") (pintype "passive"))
      (node (ref "R2") (pin "2") (pinfunction "2_2") (pintype "passive"))
    )
    (net (code "44") (name "Net-(Q1-Q2)") (class "Default")
      (node (ref "C10") (pin "1") (pinfunction "1_1") (pintype "passive"))
      (node (ref "Q1") (pin "3") (pinfunction "Q2_3") (pintype "passive"))
      (node (ref "U1") (pin "5") (pinfunction "PH0/OSC_IN_5") (pintype "input"))
    )
    (net (code "45") (name "Net-(T1-G)") (class "Default")
      (node (ref "D1") (pin "A") (pinfunction "A_A") (pintype "passive"))
      (node (ref "R8") (pin "2") (pinfunction "2_2") (pintype "passive"))
      (node (ref "T1") (pin "3") (pinfunction "G_3") (pintype "passive"))
    )
    (net (code "46") (name "Net-(U1B-VCAP_1)") (class "Default")
      (node (ref "C12") (pin "1") (pinfunction "1_1") (pintype "passive"))
      (node (ref "U1") (pin "31") (pinfunction "VCAP_1_31") (pintype "power_in"))
    )
    (net (code "47") (name "Net-(U1B-VCAP_2)") (class "Default")
      (node (ref "C9") (pin "1") (pinfunction "1_1") (pintype "passive"))
      (node (ref "U1") (pin "47") (pinfunction "VCAP_2_47") (pintype "power_in"))
    )
    (net (code "48") (name "Net-(U1H-PH1{slash}OSC_OUT)") (class "Default")
      (node (ref "R2") (pin "1") (pinfunction "1_1") (pintype "passive"))
      (node (ref "U1") (pin "6") (pinfunction "PH1/OSC_OUT_6") (pintype "output"))
    )
    (net (code "49") (name "Net-(U1I-BOOT0)") (class "Default")
      (node (ref "R3") (pin "1") (pinfunction "1_1") (pintype "passive"))
      (node (ref "U1") (pin "60") (pinfunction "BOOT0_60") (pintype "input"))
    )
    (net (code "50") (name "Net-(U2-FB)") (class "Default")
      (node (ref "R12") (pin "1") (pinfunction "1_1") (pintype "passive"))
      (node (ref "R9") (pin "2") (pinfunction "2_2") (pintype "passive"))
      (node (ref "U2") (pin "2") (pinfunction "FB_2") (pintype "input"))
    )
    (net (code "51") (name "Net-(U2-PG)") (class "Default")
      (node (ref "R11") (pin "1") (pinfunction "1_1") (pintype "passive"))
      (node (ref "U2") (pin "3") (pinfunction "PG_3") (pintype "output"))
    )
    (net (code "52") (name "Net-(U2-SS)") (class "Default")
      (node (ref "C16") (pin "1") (pinfunction "1_1") (pintype "passive"))
      (node (ref "U2") (pin "1") (pinfunction "SS_1") (pintype "passive"))
    )
    (net (code "53") (name "Net-(U3-FB)") (class "Default")
      (node (ref "R10") (pin "2") (pinfunction "2_2") (pintype "passive"))
      (node (ref "R14") (pin "1") (pinfunction "1_1") (pintype "passive"))
      (node (ref "U3") (pin "2") (pinfunction "FB_2") (pintype "input"))
    )
    (net (code "54") (name "Net-(U3-PG)") (class "Default")
      (node (ref "R13") (pin "1") (pinfunction "1_1") (pintype "passive"))
      (node (ref "U3") (pin "3") (pinfunction "PG_3") (pintype "output"))
    )
    (net (code "55") (name "Net-(U3-SS)") (class "Default")
      (node (ref "C17") (pin "1") (pinfunction "1_1") (pintype "passive"))
      (node (ref "U3") (pin "1") (pinfunction "SS_1") (pintype "passive"))
    )
    (net (code "56") (name "Net-(U5-D1C)") (class "Default")
      (node (ref "K1") (pin "D+") (pinfunction "D+_D+") (pintype "passive"))
      (node (ref "U5") (pin "6") (pinfunction "D1C_6") (pintype "bidirectional"))
    )
    (net (code "57") (name "Net-(U5-D2C)") (class "Default")
      (node (ref "K1") (pin "D-") (pinfunction "D-_D-") (pintype "passive"))
      (node (ref "U5") (pin "4") (pinfunction "D2C_4") (pintype "bidirectional"))
    )
    (net (code "58") (name "Net-(U6-CANH)") (class "Default")
      (node (ref "L1") (pin "1") (pinfunction "1_1") (pintype "passive"))
      (node (ref "U6") (pin "P7") (pinfunction "CANH_P7") (pintype "bidirectional"))
    )
    (net (code "59") (name "Net-(U6-CANL)") (class "Default")
      (node (ref "L1") (pin "2") (pinfunction "2_2") (pintype "passive"))
      (node (ref "U6") (pin "P6") (pinfunction "CANL_P6") (pintype "bidirectional"))
    )
    (net (code "60") (name "PLUS") (class "Default")
      (node (ref "J2") (pin "11") (pinfunction "1_11") (pintype "passive"))
      (node (ref "U4") (pin "5") (pinfunction "IN4_5") (pintype "bidirectional"))
    )
    (net (code "61") (name "SHIFT_DOWN") (class "Default")
      (node (ref "J2") (pin "7") (pinfunction "1_7") (pintype "passive"))
      (node (ref "U4") (pin "2") (pinfunction "IN1_2") (pintype "bidirectional"))
    )
    (net (code "62") (name "SHIFT_UP") (class "Default")
      (node (ref "J2") (pin "10") (pinfunction "1_10") (pintype "passive"))
      (node (ref "U4") (pin "4") (pinfunction "IN3_4") (pintype "bidirectional"))
    )
    (net (code "63") (name "SWCLK") (class "Default")
      (node (ref "R21") (pin "2") (pinfunction "2_2") (pintype "passive"))
      (node (ref "SV1") (pin "9") (pinfunction "9_9") (pintype "passive"))
      (node (ref "U1") (pin "49") (pinfunction "PA14_49") (pintype "bidirectional"))
    )
    (net (code "64") (name "SWDIO") (class "Default")
      (node (ref "R22") (pin "2") (pinfunction "2_2") (pintype "passive"))
      (node (ref "SV1") (pin "7") (pinfunction "7_7") (pintype "passive"))
      (node (ref "U1") (pin "46") (pinfunction "PA13_46") (pintype "bidirectional"))
    )
    (net (code "65") (name "SWO") (class "Default")
      (node (ref "R20") (pin "2") (pinfunction "2_2") (pintype "passive"))
      (node (ref "SV1") (pin "13") (pinfunction "13_13") (pintype "passive"))
      (node (ref "U1") (pin "55") (pinfunction "PB3_55") (pintype "bidirectional"))
    )
    (net (code "66") (name "UART4_RX") (class "Default")
      (node (ref "DISPLAY") (pin "P$11") (pinfunction "TXD(SPIMO)_P$11") (pintype "bidirectional"))
      (node (ref "U1") (pin "52") (pinfunction "PC11_52") (pintype "bidirectional"))
    )
    (net (code "67") (name "UART4_TX") (class "Default")
      (node (ref "DISPLAY") (pin "P$10") (pinfunction "RXD(DORD)_P$10") (pintype "bidirectional"))
      (node (ref "U1") (pin "51") (pinfunction "PC10_51") (pintype "bidirectional"))
    )
    (net (code "68") (name "USB_OTG_FS_DM") (class "Default")
      (node (ref "U1") (pin "44") (pinfunction "PA11_44") (pintype "bidirectional"))
      (node (ref "U5") (pin "3") (pinfunction "D2I_3") (pintype "bidirectional"))
    )
    (net (code "69") (name "USB_OTG_FS_DP") (class "Default")
      (node (ref "U1") (pin "45") (pinfunction "PA12_45") (pintype "bidirectional"))
      (node (ref "U5") (pin "1") (pinfunction "D1I_1") (pintype "bidirectional"))
    )
    (net (code "70") (name "USB_OTG_FS_ID") (class "Default")
      (node (ref "K1") (pin "ID") (pinfunction "ID_ID") (pintype "passive"))
      (node (ref "U1") (pin "43") (pinfunction "PA10_43") (pintype "bidirectional"))
    )
    (net (code "71") (name "VCC") (class "Default")
      (node (ref "C14") (pin "1") (pinfunction "1_1") (pintype "passive"))
      (node (ref "C15") (pin "1") (pinfunction "1_1") (pintype "passive"))
      (node (ref "D1") (pin "C") (pinfunction "C_C") (pintype "passive"))
      (node (ref "D2") (pin "C") (pinfunction "2_C") (pintype "passive"))
      (node (ref "T1") (pin "4") (pinfunction "S_4") (pintype "passive"))
      (node (ref "U2") (pin "7") (pinfunction "EN_7") (pintype "input"))
      (node (ref "U2") (pin "8") (pinfunction "VIN_8") (pintype "power_in"))
      (node (ref "U3") (pin "8") (pinfunction "VIN_8") (pintype "power_in"))
    )
    (net (code "72") (name "V_IN") (class "Default")
      (node (ref "J2") (pin "1") (pinfunction "1_1") (pintype "passive"))
      (node (ref "T1") (pin "1") (pinfunction "D_1") (pintype "passive"))
      (node (ref "T1") (pin "2") (pinfunction "D_2") (pintype "passive"))
      (node (ref "T1") (pin "5") (pinfunction "D_5") (pintype "passive"))
      (node (ref "T1") (pin "6") (pinfunction "D_6") (pintype "passive"))
    )
    (net (code "73") (name "unconnected-(DISPLAY-ADR0(CLK)-PadP$9)") (class "Default")
      (node (ref "DISPLAY") (pin "P$9") (pinfunction "ADR0(CLK)_P$9") (pintype "bidirectional"))
    )
    (net (code "74") (name "unconnected-(DISPLAY-ADR1(CPOL)-PadP$14)") (class "Default")
      (node (ref "DISPLAY") (pin "P$14") (pinfunction "ADR1(CPOL)_P$14") (pintype "bidirectional"))
    )
    (net (code "75") (name "unconnected-(DISPLAY-ADR2(CPHA)-PadP$15)") (class "Default")
      (node (ref "DISPLAY") (pin "P$15") (pinfunction "ADR2(CPHA)_P$15") (pintype "bidirectional"))
    )
    (net (code "76") (name "unconnected-(DISPLAY-BUZZ-PadP$16)") (class "Default")
      (node (ref "DISPLAY") (pin "P$16") (pinfunction "BUZZ_P$16") (pintype "bidirectional"))
    )
    (net (code "77") (name "unconnected-(DISPLAY-DPOM-PadP$13)") (class "Default")
      (node (ref "DISPLAY") (pin "P$13") (pinfunction "DPOM_P$13") (pintype "bidirectional"))
    )
    (net (code "78") (name "unconnected-(DISPLAY-DPROT-PadP$17)") (class "Default")
      (node (ref "DISPLAY") (pin "P$17") (pinfunction "DPROT_P$17") (pintype "bidirectional"))
    )
    (net (code "79") (name "unconnected-(DISPLAY-EN485-PadP$12)") (class "Default")
      (node (ref "DISPLAY") (pin "P$12") (pinfunction "EN485_P$12") (pintype "bidirectional"))
    )
    (net (code "80") (name "unconnected-(DISPLAY-TEST_SBUF-PadP$20)") (class "Default")
      (node (ref "DISPLAY") (pin "P$20") (pinfunction "TEST_SBUF_P$20") (pintype "bidirectional"))
    )
    (net (code "81") (name "unconnected-(DISPLAY-WP-PadP$19)") (class "Default")
      (node (ref "DISPLAY") (pin "P$19") (pinfunction "WP_P$19") (pintype "bidirectional"))
    )
    (net (code "82") (name "unconnected-(J1G-1-Pad15)") (class "Default")
      (node (ref "J1") (pin "15") (pinfunction "1_15") (pintype "passive"))
    )
    (net (code "83") (name "unconnected-(J1H-1-Pad16)") (class "Default")
      (node (ref "J1") (pin "16") (pinfunction "1_16") (pintype "passive"))
    )
    (net (code "84") (name "unconnected-(K1-PadVCC)") (class "Default")
      (node (ref "K1") (pin "VCC") (pinfunction "VCC_VCC") (pintype "passive"))
    )
    (net (code "85") (name "unconnected-(SV1-Pad3)") (class "Default")
      (node (ref "SV1") (pin "3") (pinfunction "3_3") (pintype "passive"))
    )
    (net (code "86") (name "unconnected-(SV1-Pad5)") (class "Default")
      (node (ref "SV1") (pin "5") (pinfunction "5_5") (pintype "passive"))
    )
    (net (code "87") (name "unconnected-(SV1-Pad11)") (class "Default")
      (node (ref "SV1") (pin "11") (pinfunction "11_11") (pintype "passive"))
    )
    (net (code "88") (name "unconnected-(SV1-Pad17)") (class "Default")
      (node (ref "SV1") (pin "17") (pinfunction "17_17") (pintype "passive"))
    )
    (net (code "89") (name "unconnected-(SV1-Pad19)") (class "Default")
      (node (ref "SV1") (pin "19") (pinfunction "19_19") (pintype "passive"))
    )
    (net (code "90") (name "unconnected-(U1C-PA8-Pad41)") (class "Default")
      (node (ref "U1") (pin "41") (pinfunction "PA8_41") (pintype "bidirectional"))
    )
    (net (code "91") (name "unconnected-(U1C-PA9-Pad42)") (class "Default")
      (node (ref "U1") (pin "42") (pinfunction "PA9_42") (pintype "bidirectional"))
    )
    (net (code "92") (name "unconnected-(U1D-PA0-Pad14)") (class "Default")
      (node (ref "U1") (pin "14") (pinfunction "PA0_14") (pintype "bidirectional"))
    )
    (net (code "93") (name "unconnected-(U1D-PA1-Pad15)") (class "Default")
      (node (ref "U1") (pin "15") (pinfunction "PA1_15") (pintype "bidirectional"))
    )
    (net (code "94") (name "unconnected-(U1D-PA2-Pad16)") (class "Default")
      (node (ref "U1") (pin "16") (pinfunction "PA2_16") (pintype "bidirectional"))
    )
    (net (code "95") (name "unconnected-(U1D-PA3-Pad17)") (class "Default")
      (node (ref "U1") (pin "17") (pinfunction "PA3_17") (pintype "bidirectional"))
    )
    (net (code "96") (name "unconnected-(U1D-PA5-Pad21)") (class "Default")
      (node (ref "U1") (pin "21") (pinfunction "PA5_21") (pintype "bidirectional"))
    )
    (net (code "97") (name "unconnected-(U1D-PA6-Pad22)") (class "Default")
      (node (ref "U1") (pin "22") (pinfunction "PA6_22") (pintype "bidirectional"))
    )
    (net (code "98") (name "unconnected-(U1D-PA7-Pad23)") (class "Default")
      (node (ref "U1") (pin "23") (pinfunction "PA7_23") (pintype "bidirectional"))
    )
    (net (code "99") (name "unconnected-(U1E-PB11-Pad30)") (class "Default")
      (node (ref "U1") (pin "30") (pinfunction "PB11_30") (pintype "bidirectional"))
    )
    (net (code "100") (name "unconnected-(U1F-PB4-Pad56)") (class "Default")
      (node (ref "U1") (pin "56") (pinfunction "PB4_56") (pintype "bidirectional"))
    )
    (net (code "101") (name "unconnected-(U1F-PB5-Pad57)") (class "Default")
      (node (ref "U1") (pin "57") (pinfunction "PB5_57") (pintype "bidirectional"))
    )
    (net (code "102") (name "unconnected-(U1J-PC8-Pad39)") (class "Default")
      (node (ref "U1") (pin "39") (pinfunction "PC8_39") (pintype "bidirectional"))
    )
    (net (code "103") (name "unconnected-(U1J-PC9-Pad40)") (class "Default")
      (node (ref "U1") (pin "40") (pinfunction "PC9_40") (pintype "bidirectional"))
    )
    (net (code "104") (name "unconnected-(U1J-PC12-Pad53)") (class "Default")
      (node (ref "U1") (pin "53") (pinfunction "PC12_53") (pintype "bidirectional"))
    )
    (net (code "105") (name "unconnected-(U1J-PC13-Pad2)") (class "Default")
      (node (ref "U1") (pin "2") (pinfunction "PC13_2") (pintype "bidirectional"))
    )
    (net (code "106") (name "unconnected-(U1J-PC14{slash}OSC32_IN-Pad3)") (class "Default")
      (node (ref "U1") (pin "3") (pinfunction "PC14/OSC32_IN_3") (pintype "bidirectional"))
    )
    (net (code "107") (name "unconnected-(U1J-PC15{slash}OSC32_OUT-Pad4)") (class "Default")
      (node (ref "U1") (pin "4") (pinfunction "PC15/OSC32_OUT_4") (pintype "bidirectional"))
    )
    (net (code "108") (name "unconnected-(U1K-PC1-Pad9)") (class "Default")
      (node (ref "U1") (pin "9") (pinfunction "PC1_9") (pintype "bidirectional"))
    )
    (net (code "109") (name "unconnected-(U1K-PC2-Pad10)") (class "Default")
      (node (ref "U1") (pin "10") (pinfunction "PC2_10") (pintype "bidirectional"))
    )
    (net (code "110") (name "unconnected-(U1K-PC3-Pad11)") (class "Default")
      (node (ref "U1") (pin "11") (pinfunction "PC3_11") (pintype "bidirectional"))
    )
    (net (code "111") (name "unconnected-(U1K-PC6-Pad37)") (class "Default")
      (node (ref "U1") (pin "37") (pinfunction "PC6_37") (pintype "bidirectional"))
    )
    (net (code "112") (name "unconnected-(U1K-PC7-Pad38)") (class "Default")
      (node (ref "U1") (pin "38") (pinfunction "PC7_38") (pintype "bidirectional"))
    )
    (net (code "113") (name "unconnected-(U4-IN6-Pad7)") (class "Default")
      (node (ref "U4") (pin "7") (pinfunction "IN6_7") (pintype "bidirectional"))
    )
    (net (code "114") (name "unconnected-(U4-IN7-Pad8)") (class "Default")
      (node (ref "U4") (pin "8") (pinfunction "IN7_8") (pintype "bidirectional"))
    )
    (net (code "115") (name "unconnected-(U4-IN8-Pad9)") (class "Default")
      (node (ref "U4") (pin "9") (pinfunction "IN8_9") (pintype "bidirectional"))
    )
    (net (code "116") (name "unconnected-(U4-OUT6-Pad14)") (class "Default")
      (node (ref "U4") (pin "14") (pinfunction "OUT6_14") (pintype "bidirectional"))
    )
    (net (code "117") (name "unconnected-(U4-OUT7-Pad13)") (class "Default")
      (node (ref "U4") (pin "13") (pinfunction "OUT7_13") (pintype "bidirectional"))
    )
    (net (code "118") (name "unconnected-(U4-OUT8-Pad12)") (class "Default")
      (node (ref "U4") (pin "12") (pinfunction "OUT8_12") (pintype "bidirectional"))
    )
    (net (code "119") (name "unconnected-(U8-P12-Pad17)") (class "Default")
      (node (ref "U8") (pin "17") (pinfunction "P12_17") (pintype "passive"))
    )
    (net (code "120") (name "unconnected-(U8-P13-Pad18)") (class "Default")
      (node (ref "U8") (pin "18") (pinfunction "P13_18") (pintype "passive"))
    )
    (net (code "121") (name "unconnected-(U8-P14-Pad19)") (class "Default")
      (node (ref "U8") (pin "19") (pinfunction "P14_19") (pintype "passive"))
    )
    (net (code "122") (name "unconnected-(U8-P15-Pad20)") (class "Default")
      (node (ref "U8") (pin "20") (pinfunction "P15_20") (pintype "passive"))
    )
    (net (code "123") (name "unconnected-(U8-~{INT}-Pad1)") (class "Default")
      (node (ref "U8") (pin "1") (pinfunction "~{INT}_1") (pintype "bidirectional"))
    )
    (net (code "124") (name "~{MAX_CH}") (class "Default")
      (node (ref "R23") (pin "1") (pinfunction "1_1") (pintype "passive"))
      (node (ref "U1") (pin "29") (pinfunction "PB10_29") (pintype "bidirectional"))
      (node (ref "U4") (pin "11") (pinfunction "~{CH}_11") (pintype "bidirectional"))
    )
    (net (code "125") (name "~{RESET}") (class "Default")
      (node (ref "C13") (pin "1") (pinfunction "1_1") (pintype "passive"))
      (node (ref "R1") (pin "2") (pinfunction "2_2") (pintype "passive"))
      (node (ref "R19") (pin "2") (pinfunction "2_2") (pintype "passive"))
      (node (ref "SV1") (pin "15") (pinfunction "15_15") (pintype "passive"))
      (node (ref "U1") (pin "7") (pinfunction "NRST_7") (pintype "input"))
    )
  )
)
